# micron_P4.net
KiCad netlist of a schematic drawn in Altium Designer
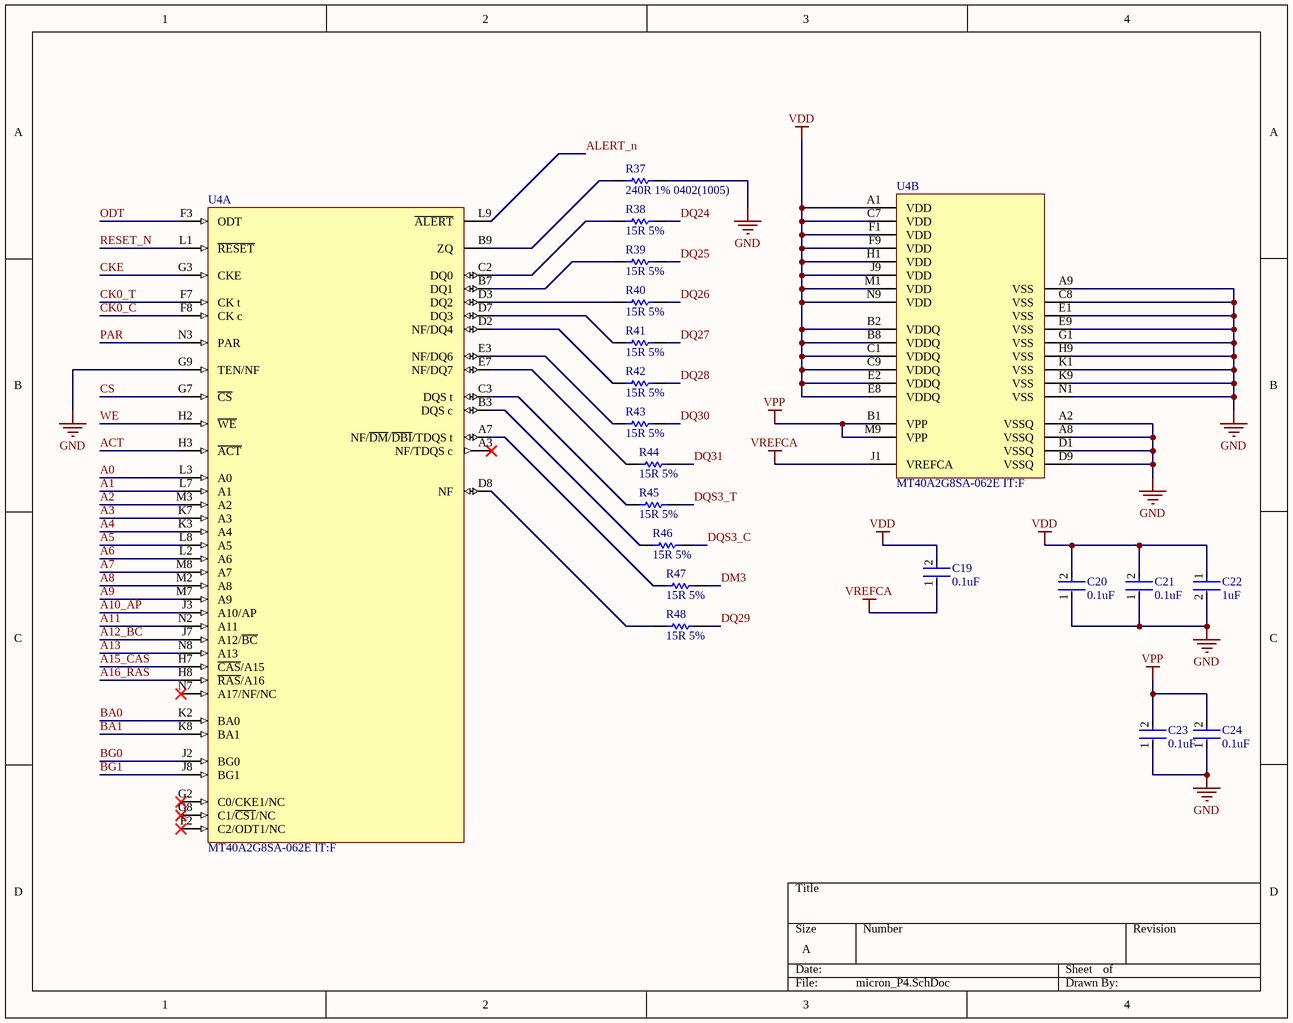
[diagram p0: micron_P4.SchDoc]

(export (version "E")
  (design (tool "Eeschema 10.0.6"))
  (components
    (comp (ref "C19")
      (value "0.1uF")
      (footprint "FP-GRM15-MFG")
      (description "CAP CER 0.1UF 16V X7R 0402")
      (fields (field (name "MANUFACTURER PART NUMBER") "GRM155R71C104KA88D") (field (name "TOLERANCE") "10%"))
      (libsource (lib "Altium Content Vault") (part "236180d848d6139a670b325ea6854c9"))
    )
    (comp (ref "C20")
      (value "0.1uF")
      (footprint "FP-GRM15-MFG")
      (description "CAP CER 0.1UF 16V X7R 0402")
      (fields (field (name "MANUFACTURER PART NUMBER") "GRM155R71C104KA88D") (field (name "TOLERANCE") "10%"))
      (libsource (lib "Altium Content Vault") (part "236180d848d6139a670b325ea6854c9"))
    )
    (comp (ref "C21")
      (value "0.1uF")
      (footprint "FP-GRM15-MFG")
      (description "CAP CER 0.1UF 16V X7R 0402")
      (fields (field (name "MANUFACTURER PART NUMBER") "GRM155R71C104KA88D") (field (name "TOLERANCE") "10%"))
      (libsource (lib "Altium Content Vault") (part "236180d848d6139a670b325ea6854c9"))
    )
    (comp (ref "C22")
      (value "1uF")
      (footprint "FP-CL511-IPC_C")
      (description "Cap Ceramic 1uF 10V X5R ±10% SMD 0402 +85°C Paper T/R")
      (fields (field (name "TOLERANCE") "10%"))
      (libsource (lib "Altium Content Vault") (part "b4654b650e69147ec39a6b967a45e02"))
    )
    (comp (ref "C23")
      (value "0.1uF")
      (footprint "FP-GRM15-MFG")
      (description "CAP CER 0.1UF 16V X7R 0402")
      (fields (field (name "MANUFACTURER PART NUMBER") "GRM155R71C104KA88D") (field (name "TOLERANCE") "10%"))
      (libsource (lib "Altium Content Vault") (part "236180d848d6139a670b325ea6854c9"))
    )
    (comp (ref "C24")
      (value "0.1uF")
      (footprint "FP-GRM15-MFG")
      (description "CAP CER 0.1UF 16V X7R 0402")
      (fields (field (name "MANUFACTURER PART NUMBER") "GRM155R71C104KA88D") (field (name "TOLERANCE") "10%"))
      (libsource (lib "Altium Content Vault") (part "236180d848d6139a670b325ea6854c9"))
    )
    (comp (ref "R37")
      (value "240R 1% 0402(1005)")
      (footprint "RESC0402(1005)_L")
      (description "240R 0.063W 1% 0402 (1005 Metric)  SMD")
      (fields (field (name "POWER") "0.063 W") (field (name "TOLERANCE") "1 %"))
      (libsource (lib "Altium Content Vault") (part "RES"))
    )
    (comp (ref "R38")
      (value "15R 5%")
      (footprint "RESC1005X40X25LL05T10")
      (fields (field (name "MANUFACTURER") "Yageo / Phycomp") (field (name "PART NUMBER") "RC0402FR-0715RL"))
      (libsource (lib "Altium Content Vault") (part "RES"))
    )
    (comp (ref "R39")
      (value "15R 5%")
      (footprint "RESC1005X40X25LL05T10")
      (fields (field (name "MANUFACTURER") "Yageo / Phycomp") (field (name "PART NUMBER") "RC0402FR-0715RL"))
      (libsource (lib "Altium Content Vault") (part "RES"))
    )
    (comp (ref "R40")
      (value "15R 5%")
      (footprint "RESC1005X40X25LL05T10")
      (fields (field (name "MANUFACTURER") "Yageo / Phycomp") (field (name "PART NUMBER") "RC0402FR-0715RL"))
      (libsource (lib "Altium Content Vault") (part "RES"))
    )
    (comp (ref "R41")
      (value "15R 5%")
      (footprint "RESC1005X40X25LL05T10")
      (fields (field (name "MANUFACTURER") "Yageo / Phycomp") (field (name "PART NUMBER") "RC0402FR-0715RL"))
      (libsource (lib "Altium Content Vault") (part "RES"))
    )
    (comp (ref "R42")
      (value "15R 5%")
      (footprint "RESC1005X40X25LL05T10")
      (fields (field (name "MANUFACTURER") "Yageo / Phycomp") (field (name "PART NUMBER") "RC0402FR-0715RL"))
      (libsource (lib "Altium Content Vault") (part "RES"))
    )
    (comp (ref "R43")
      (value "15R 5%")
      (footprint "RESC1005X40X25LL05T10")
      (fields (field (name "MANUFACTURER") "Yageo / Phycomp") (field (name "PART NUMBER") "RC0402FR-0715RL"))
      (libsource (lib "Altium Content Vault") (part "RES"))
    )
    (comp (ref "R44")
      (value "15R 5%")
      (footprint "RESC1005X40X25LL05T10")
      (fields (field (name "MANUFACTURER") "Yageo / Phycomp") (field (name "PART NUMBER") "RC0402FR-0715RL"))
      (libsource (lib "Altium Content Vault") (part "RES"))
    )
    (comp (ref "R45")
      (value "15R 5%")
      (footprint "RESC1005X40X25LL05T10")
      (fields (field (name "MANUFACTURER") "Yageo / Phycomp") (field (name "PART NUMBER") "RC0402FR-0715RL"))
      (libsource (lib "Altium Content Vault") (part "RES"))
    )
    (comp (ref "R46")
      (value "15R 5%")
      (footprint "RESC1005X40X25LL05T10")
      (fields (field (name "MANUFACTURER") "Yageo / Phycomp") (field (name "PART NUMBER") "RC0402FR-0715RL"))
      (libsource (lib "Altium Content Vault") (part "RES"))
    )
    (comp (ref "R47")
      (value "15R 5%")
      (footprint "RESC1005X40X25LL05T10")
      (fields (field (name "MANUFACTURER") "Yageo / Phycomp") (field (name "PART NUMBER") "RC0402FR-0715RL"))
      (libsource (lib "Altium Content Vault") (part "RES"))
    )
    (comp (ref "R48")
      (value "15R 5%")
      (footprint "RESC1005X40X25LL05T10")
      (fields (field (name "MANUFACTURER") "Yageo / Phycomp") (field (name "PART NUMBER") "RC0402FR-0715RL"))
      (libsource (lib "Altium Content Vault") (part "RES"))
    )
    (comp (ref "U4")
      (value "MT40A2G8SA-062E IT:F")
      (footprint "SA_MFG")
      (description "DRAMChip DDR4 SDRAM 16Gbit 2Gx8 1.2V 78-Pin FBGA Tray")
      (libsource (lib "Altium Content Vault") (part "d28cb998757b614ee3280f10a38a3b1"))
    )
  )
  (nets
    (net (code "1") (name "/A0") (class "Default")
      (node (ref "U4") (pin "L3") (pinfunction "A0_L3") (pintype "input"))
    )
    (net (code "2") (name "/A1") (class "Default")
      (node (ref "U4") (pin "L7") (pinfunction "A1_L7") (pintype "input"))
    )
    (net (code "3") (name "/A2") (class "Default")
      (node (ref "U4") (pin "M3") (pinfunction "A2_M3") (pintype "input"))
    )
    (net (code "4") (name "/A3") (class "Default")
      (node (ref "U4") (pin "K7") (pinfunction "A3_K7") (pintype "input"))
    )
    (net (code "5") (name "/A4") (class "Default")
      (node (ref "U4") (pin "K3") (pinfunction "A4_K3") (pintype "input"))
    )
    (net (code "6") (name "/A5") (class "Default")
      (node (ref "U4") (pin "L8") (pinfunction "A5_L8") (pintype "input"))
    )
    (net (code "7") (name "/A6") (class "Default")
      (node (ref "U4") (pin "L2") (pinfunction "A6_L2") (pintype "input"))
    )
    (net (code "8") (name "/A7") (class "Default")
      (node (ref "U4") (pin "M8") (pinfunction "A7_M8") (pintype "input"))
    )
    (net (code "9") (name "/A8") (class "Default")
      (node (ref "U4") (pin "M2") (pinfunction "A8_M2") (pintype "input"))
    )
    (net (code "10") (name "/A9") (class "Default")
      (node (ref "U4") (pin "M7") (pinfunction "A9_M7") (pintype "input"))
    )
    (net (code "11") (name "/A10_AP") (class "Default")
      (node (ref "U4") (pin "J3") (pinfunction "A10/AP_J3") (pintype "input"))
    )
    (net (code "12") (name "/A11") (class "Default")
      (node (ref "U4") (pin "N2") (pinfunction "A11_N2") (pintype "input"))
    )
    (net (code "13") (name "/A12_BC") (class "Default")
      (node (ref "U4") (pin "J7") (pinfunction "A12/~{BC}_J7") (pintype "input"))
    )
    (net (code "14") (name "/A13") (class "Default")
      (node (ref "U4") (pin "N8") (pinfunction "A13_N8") (pintype "input"))
    )
    (net (code "15") (name "/A15_CAS") (class "Default")
      (node (ref "U4") (pin "H7") (pinfunction "~{CAS}/A15_H7") (pintype "input"))
    )
    (net (code "16") (name "/A16_RAS") (class "Default")
      (node (ref "U4") (pin "H8") (pinfunction "~{RAS}/A16_H8") (pintype "input"))
    )
    (net (code "17") (name "/ACT") (class "Default")
      (node (ref "U4") (pin "H3") (pinfunction "~{ACT}_H3") (pintype "input"))
    )
    (net (code "18") (name "/ALERT_n") (class "Default")
      (node (ref "U4") (pin "L9") (pinfunction "~{ALERT}_L9") (pintype "open_collector"))
    )
    (net (code "19") (name "/BA0") (class "Default")
      (node (ref "U4") (pin "K2") (pinfunction "BA0_K2") (pintype "input"))
    )
    (net (code "20") (name "/BA1") (class "Default")
      (node (ref "U4") (pin "K8") (pinfunction "BA1_K8") (pintype "input"))
    )
    (net (code "21") (name "/BG0") (class "Default")
      (node (ref "U4") (pin "J2") (pinfunction "BG0_J2") (pintype "input"))
    )
    (net (code "22") (name "/BG1") (class "Default")
      (node (ref "U4") (pin "J8") (pinfunction "BG1_J8") (pintype "input"))
    )
    (net (code "23") (name "/CK0_C") (class "Default")
      (node (ref "U4") (pin "F8") (pinfunction "CK_c_F8") (pintype "input"))
    )
    (net (code "24") (name "/CK0_T") (class "Default")
      (node (ref "U4") (pin "F7") (pinfunction "CK_t_F7") (pintype "input"))
    )
    (net (code "25") (name "/CKE") (class "Default")
      (node (ref "U4") (pin "G3") (pinfunction "CKE_G3") (pintype "input"))
    )
    (net (code "26") (name "/CS") (class "Default")
      (node (ref "U4") (pin "G7") (pinfunction "~{CS}_G7") (pintype "input"))
    )
    (net (code "27") (name "/DM3") (class "Default")
      (node (ref "R47") (pin "2") (pinfunction "2_2") (pintype "passive"))
    )
    (net (code "28") (name "/DQ24") (class "Default")
      (node (ref "R38") (pin "2") (pinfunction "2_2") (pintype "passive"))
    )
    (net (code "29") (name "/DQ25") (class "Default")
      (node (ref "R39") (pin "2") (pinfunction "2_2") (pintype "passive"))
    )
    (net (code "30") (name "/DQ26") (class "Default")
      (node (ref "R40") (pin "2") (pinfunction "2_2") (pintype "passive"))
    )
    (net (code "31") (name "/DQ27") (class "Default")
      (node (ref "R41") (pin "2") (pinfunction "2_2") (pintype "passive"))
    )
    (net (code "32") (name "/DQ28") (class "Default")
      (node (ref "R42") (pin "2") (pinfunction "2_2") (pintype "passive"))
    )
    (net (code "33") (name "/DQ29") (class "Default")
      (node (ref "R48") (pin "2") (pinfunction "2_2") (pintype "passive"))
    )
    (net (code "34") (name "/DQ30") (class "Default")
      (node (ref "R43") (pin "2") (pinfunction "2_2") (pintype "passive"))
    )
    (net (code "35") (name "/DQ31") (class "Default")
      (node (ref "R44") (pin "2") (pinfunction "2_2") (pintype "passive"))
    )
    (net (code "36") (name "/DQS3_C") (class "Default")
      (node (ref "R46") (pin "2") (pinfunction "2_2") (pintype "passive"))
    )
    (net (code "37") (name "/DQS3_T") (class "Default")
      (node (ref "R45") (pin "2") (pinfunction "2_2") (pintype "passive"))
    )
    (net (code "38") (name "/ODT") (class "Default")
      (node (ref "U4") (pin "F3") (pinfunction "ODT_F3") (pintype "input"))
    )
    (net (code "39") (name "/PAR") (class "Default")
      (node (ref "U4") (pin "N3") (pinfunction "PAR_N3") (pintype "input"))
    )
    (net (code "40") (name "/RESET_N") (class "Default")
      (node (ref "U4") (pin "L1") (pinfunction "~{RESET}_L1") (pintype "input"))
    )
    (net (code "41") (name "/WE") (class "Default")
      (node (ref "U4") (pin "H2") (pinfunction "~{WE}_H2") (pintype "input"))
    )
    (net (code "42") (name "GND") (class "Default")
      (node (ref "C20") (pin "1") (pinfunction "1_1") (pintype "passive"))
      (node (ref "C21") (pin "1") (pinfunction "1_1") (pintype "passive"))
      (node (ref "C22") (pin "2") (pinfunction "2_2") (pintype "passive"))
      (node (ref "C23") (pin "1") (pinfunction "1_1") (pintype "passive"))
      (node (ref "C24") (pin "1") (pinfunction "1_1") (pintype "passive"))
      (node (ref "R37") (pin "2") (pinfunction "2_2") (pintype "passive"))
      (node (ref "U4") (pin "A2") (pinfunction "VSSQ_A2") (pintype "power_in"))
      (node (ref "U4") (pin "A8") (pinfunction "VSSQ_A8") (pintype "power_in"))
      (node (ref "U4") (pin "A9") (pinfunction "VSS_A9") (pintype "power_in"))
      (node (ref "U4") (pin "C8") (pinfunction "VSS_C8") (pintype "power_in"))
      (node (ref "U4") (pin "D1") (pinfunction "VSSQ_D1") (pintype "power_in"))
      (node (ref "U4") (pin "D9") (pinfunction "VSSQ_D9") (pintype "power_in"))
      (node (ref "U4") (pin "E1") (pinfunction "VSS_E1") (pintype "power_in"))
      (node (ref "U4") (pin "E9") (pinfunction "VSS_E9") (pintype "power_in"))
      (node (ref "U4") (pin "G1") (pinfunction "VSS_G1") (pintype "power_in"))
      (node (ref "U4") (pin "G9") (pinfunction "TEN/NF_G9") (pintype "input"))
      (node (ref "U4") (pin "H9") (pinfunction "VSS_H9") (pintype "power_in"))
      (node (ref "U4") (pin "K1") (pinfunction "VSS_K1") (pintype "power_in"))
      (node (ref "U4") (pin "K9") (pinfunction "VSS_K9") (pintype "power_in"))
      (node (ref "U4") (pin "N1") (pinfunction "VSS_N1") (pintype "power_in"))
    )
    (net (code "43") (name "Net-(U4A-DQ0)") (class "Default")
      (node (ref "R38") (pin "1") (pinfunction "1_1") (pintype "passive"))
      (node (ref "U4") (pin "C2") (pinfunction "DQ0_C2") (pintype "bidirectional"))
    )
    (net (code "44") (name "Net-(U4A-DQ1)") (class "Default")
      (node (ref "R39") (pin "1") (pinfunction "1_1") (pintype "passive"))
      (node (ref "U4") (pin "B7") (pinfunction "DQ1_B7") (pintype "bidirectional"))
    )
    (net (code "45") (name "Net-(U4A-DQ2)") (class "Default")
      (node (ref "R40") (pin "1") (pinfunction "1_1") (pintype "passive"))
      (node (ref "U4") (pin "D3") (pinfunction "DQ2_D3") (pintype "bidirectional"))
    )
    (net (code "46") (name "Net-(U4A-DQ3)") (class "Default")
      (node (ref "R41") (pin "1") (pinfunction "1_1") (pintype "passive"))
      (node (ref "U4") (pin "D7") (pinfunction "DQ3_D7") (pintype "bidirectional"))
    )
    (net (code "47") (name "Net-(U4A-DQS_c)") (class "Default")
      (node (ref "R46") (pin "1") (pinfunction "1_1") (pintype "passive"))
      (node (ref "U4") (pin "B3") (pinfunction "DQS_c_B3") (pintype "bidirectional"))
    )
    (net (code "48") (name "Net-(U4A-DQS_t)") (class "Default")
      (node (ref "R45") (pin "1") (pinfunction "1_1") (pintype "passive"))
      (node (ref "U4") (pin "C3") (pinfunction "DQS_t_C3") (pintype "bidirectional"))
    )
    (net (code "49") (name "Net-(U4A-NF)") (class "Default")
      (node (ref "R48") (pin "1") (pinfunction "1_1") (pintype "passive"))
      (node (ref "U4") (pin "D8") (pinfunction "NF_D8") (pintype "bidirectional"))
    )
    (net (code "50") (name "Net-(U4A-NF{slash}DQ4)") (class "Default")
      (node (ref "R42") (pin "1") (pinfunction "1_1") (pintype "passive"))
      (node (ref "U4") (pin "D2") (pinfunction "NF/DQ4_D2") (pintype "bidirectional"))
    )
    (net (code "51") (name "Net-(U4A-NF{slash}DQ6)") (class "Default")
      (node (ref "R43") (pin "1") (pinfunction "1_1") (pintype "passive"))
      (node (ref "U4") (pin "E3") (pinfunction "NF/DQ6_E3") (pintype "bidirectional"))
    )
    (net (code "52") (name "Net-(U4A-NF{slash}DQ7)") (class "Default")
      (node (ref "R44") (pin "1") (pinfunction "1_1") (pintype "passive"))
      (node (ref "U4") (pin "E7") (pinfunction "NF/DQ7_E7") (pintype "bidirectional"))
    )
    (net (code "53") (name "Net-(U4A-NF{slash}~{DM}{slash}~{DBI}{slash}TDQS_t)") (class "Default")
      (node (ref "R47") (pin "1") (pinfunction "1_1") (pintype "passive"))
      (node (ref "U4") (pin "A7") (pinfunction "NF/~{DM}/~{DBI}/TDQS_t_A7") (pintype "bidirectional"))
    )
    (net (code "54") (name "Net-(U4A-ZQ)") (class "Default")
      (node (ref "R37") (pin "1") (pinfunction "1_1") (pintype "passive"))
      (node (ref "U4") (pin "B9") (pinfunction "ZQ_B9") (pintype "passive"))
    )
    (net (code "55") (name "VDD") (class "Default")
      (node (ref "C19") (pin "2") (pinfunction "2_2") (pintype "passive"))
      (node (ref "C20") (pin "2") (pinfunction "2_2") (pintype "passive"))
      (node (ref "C21") (pin "2") (pinfunction "2_2") (pintype "passive"))
      (node (ref "C22") (pin "1") (pinfunction "1_1") (pintype "passive"))
      (node (ref "U4") (pin "A1") (pinfunction "VDD_A1") (pintype "power_in"))
      (node (ref "U4") (pin "B2") (pinfunction "VDDQ_B2") (pintype "power_in"))
      (node (ref "U4") (pin "B8") (pinfunction "VDDQ_B8") (pintype "power_in"))
      (node (ref "U4") (pin "C1") (pinfunction "VDDQ_C1") (pintype "power_in"))
      (node (ref "U4") (pin "C7") (pinfunction "VDD_C7") (pintype "power_in"))
      (node (ref "U4") (pin "C9") (pinfunction "VDDQ_C9") (pintype "power_in"))
      (node (ref "U4") (pin "E2") (pinfunction "VDDQ_E2") (pintype "power_in"))
      (node (ref "U4") (pin "E8") (pinfunction "VDDQ_E8") (pintype "power_in"))
      (node (ref "U4") (pin "F1") (pinfunction "VDD_F1") (pintype "power_in"))
      (node (ref "U4") (pin "F9") (pinfunction "VDD_F9") (pintype "power_in"))
      (node (ref "U4") (pin "H1") (pinfunction "VDD_H1") (pintype "power_in"))
      (node (ref "U4") (pin "J9") (pinfunction "VDD_J9") (pintype "power_in"))
      (node (ref "U4") (pin "M1") (pinfunction "VDD_M1") (pintype "power_in"))
      (node (ref "U4") (pin "N9") (pinfunction "VDD_N9") (pintype "power_in"))
    )
    (net (code "56") (name "VPP") (class "Default")
      (node (ref "C23") (pin "2") (pinfunction "2_2") (pintype "passive"))
      (node (ref "C24") (pin "2") (pinfunction "2_2") (pintype "passive"))
      (node (ref "U4") (pin "B1") (pinfunction "VPP_B1") (pintype "power_in"))
      (node (ref "U4") (pin "M9") (pinfunction "VPP_M9") (pintype "power_in"))
    )
    (net (code "57") (name "VREFCA") (class "Default")
      (node (ref "C19") (pin "1") (pinfunction "1_1") (pintype "passive"))
      (node (ref "U4") (pin "J1") (pinfunction "VREFCA_J1") (pintype "power_in"))
    )
    (net (code "58") (name "unconnected-(U4A-A17{slash}NF{slash}NC-PadN7)") (class "Default")
      (node (ref "U4") (pin "N7") (pinfunction "A17/NF/NC_N7") (pintype "input+no_connect"))
    )
    (net (code "59") (name "unconnected-(U4A-C0{slash}CKE1{slash}NC-PadG2)") (class "Default")
      (node (ref "U4") (pin "G2") (pinfunction "C0/CKE1/NC_G2") (pintype "input+no_connect"))
    )
    (net (code "60") (name "unconnected-(U4A-C1{slash}~{CS1}{slash}NC-PadG8)") (class "Default")
      (node (ref "U4") (pin "G8") (pinfunction "C1/~{CS1}/NC_G8") (pintype "input+no_connect"))
    )
    (net (code "61") (name "unconnected-(U4A-C2{slash}ODT1{slash}NC-PadF2)") (class "Default")
      (node (ref "U4") (pin "F2") (pinfunction "C2/ODT1/NC_F2") (pintype "input+no_connect"))
    )
    (net (code "62") (name "unconnected-(U4A-NF{slash}TDQS_c-PadA3)") (class "Default")
      (node (ref "U4") (pin "A3") (pinfunction "NF/TDQS_c_A3") (pintype "output+no_connect"))
    )
  )
)
